# Window_Comparator.net
KiCad netlist of a schematic drawn in Altium Designer
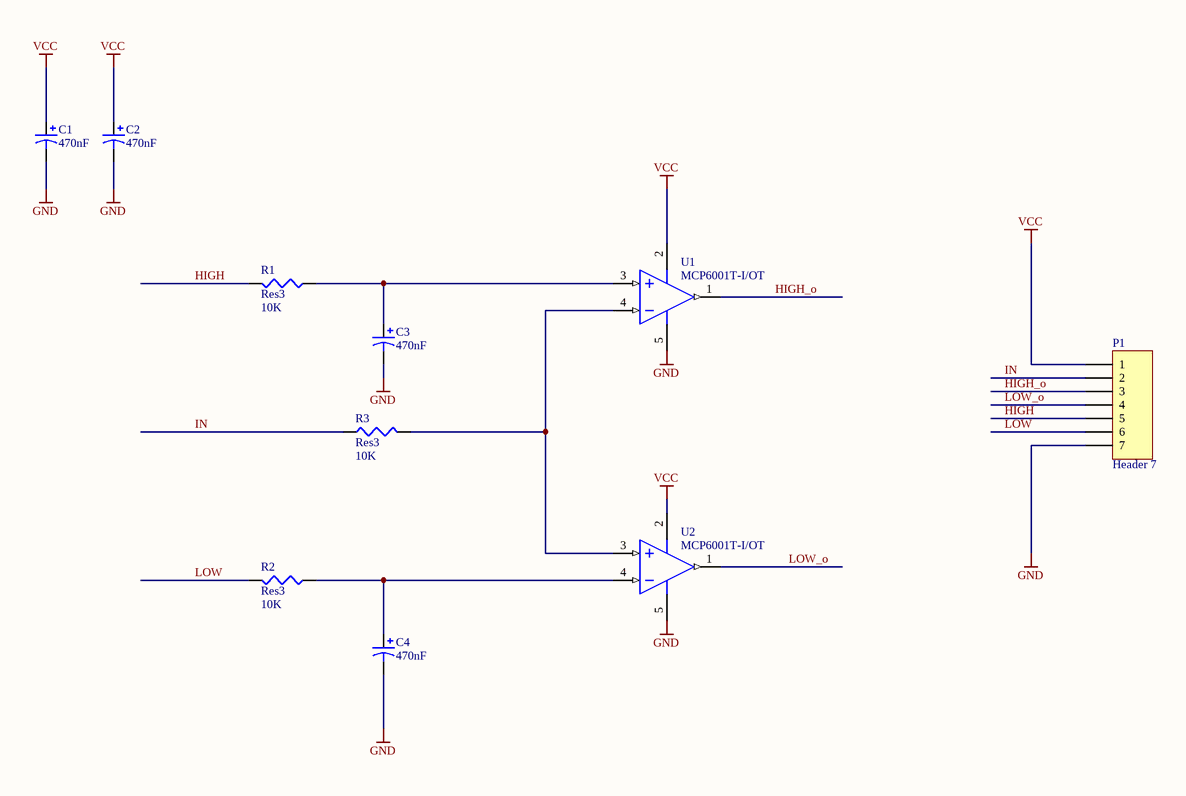
[diagram p0: Window Comparator.SchDoc]

(export (version "E")
  (design (tool "Eeschema 10.0.6"))
  (components
    (comp (ref "C1")
      (value "470nF")
      (footprint "C0805")
      (description "Polarized Capacitor (Surface Mount)")
      (fields (field (name "Comment") "Cap Pol3") (field (name "PUBLISHER") "Altium Limited"))
      (libsource (lib "Miscellaneous Devices") (part "Cap Pol3"))
    )
    (comp (ref "C2")
      (value "470nF")
      (footprint "C0805")
      (description "Polarized Capacitor (Surface Mount)")
      (fields (field (name "Comment") "Cap Pol3") (field (name "PUBLISHER") "Altium Limited"))
      (libsource (lib "Miscellaneous Devices") (part "Cap Pol3"))
    )
    (comp (ref "C3")
      (value "470nF")
      (footprint "C0805")
      (description "Polarized Capacitor (Surface Mount)")
      (fields (field (name "Comment") "Cap Pol3") (field (name "PUBLISHER") "Altium Limited"))
      (libsource (lib "Miscellaneous Devices") (part "Cap Pol3"))
    )
    (comp (ref "C4")
      (value "470nF")
      (footprint "C0805")
      (description "Polarized Capacitor (Surface Mount)")
      (fields (field (name "Comment") "Cap Pol3") (field (name "PUBLISHER") "Altium Limited"))
      (libsource (lib "Miscellaneous Devices") (part "Cap Pol3"))
    )
    (comp (ref "P1")
      (value "Header 7")
      (footprint "HDR1X7")
      (description "Header, 7-Pin")
      (fields (field (name "PUBLISHER") "Altium Limited"))
      (libsource (lib "Miscellaneous Connectors") (part "Header 7"))
    )
    (comp (ref "R1")
      (value "Res3")
      (footprint "J1-0603")
      (description "Resistor")
      (fields (field (name "ALTIUM_VALUE") "10K") (field (name "PUBLISHER") "Altium Limited"))
      (libsource (lib "Miscellaneous Devices") (part "Res3"))
    )
    (comp (ref "R2")
      (value "Res3")
      (footprint "J1-0603")
      (description "Resistor")
      (fields (field (name "ALTIUM_VALUE") "10K") (field (name "PUBLISHER") "Altium Limited"))
      (libsource (lib "Miscellaneous Devices") (part "Res3"))
    )
    (comp (ref "R3")
      (value "Res3")
      (footprint "J1-0603")
      (description "Resistor")
      (fields (field (name "ALTIUM_VALUE") "10K") (field (name "PUBLISHER") "Altium Limited"))
      (libsource (lib "Miscellaneous Devices") (part "Res3"))
    )
    (comp (ref "U1")
      (value "MCP6001T-I/OT")
      (footprint "SOT-23-OT5_N")
      (description "1 MHz, Low-Power Operational Amplifier, 5-Pin SOT-23, Industrial Temperature, Tape and Reel")
      (fields (field (name "PUBLISHER") "Altium Limited"))
      (libsource (lib "Microchip Linear Devices") (part "MCP6001T-I/OT"))
    )
    (comp (ref "U2")
      (value "MCP6001T-I/OT")
      (footprint "SOT-23-OT5_N")
      (description "1 MHz, Low-Power Operational Amplifier, 5-Pin SOT-23, Industrial Temperature, Tape and Reel")
      (fields (field (name "PUBLISHER") "Altium Limited"))
      (libsource (lib "Microchip Linear Devices") (part "MCP6001T-I/OT"))
    )
  )
  (nets
    (net (code "1") (name "/HIGH") (class "Default")
      (node (ref "P1") (pin "5") (pinfunction "5_5") (pintype "passive"))
      (node (ref "R1") (pin "2") (pinfunction "2_2") (pintype "passive"))
    )
    (net (code "2") (name "/HIGH_o") (class "Default")
      (node (ref "P1") (pin "3") (pinfunction "3_3") (pintype "passive"))
      (node (ref "U1") (pin "1") (pinfunction "VOUT_1") (pintype "output"))
    )
    (net (code "3") (name "/IN") (class "Default")
      (node (ref "P1") (pin "2") (pinfunction "2_2") (pintype "passive"))
      (node (ref "R3") (pin "1") (pinfunction "1_1") (pintype "passive"))
    )
    (net (code "4") (name "/LOW") (class "Default")
      (node (ref "P1") (pin "6") (pinfunction "6_6") (pintype "passive"))
      (node (ref "R2") (pin "2") (pinfunction "2_2") (pintype "passive"))
    )
    (net (code "5") (name "/LOW_o") (class "Default")
      (node (ref "P1") (pin "4") (pinfunction "4_4") (pintype "passive"))
      (node (ref "U2") (pin "1") (pinfunction "VOUT_1") (pintype "output"))
    )
    (net (code "6") (name "GND") (class "Default")
      (node (ref "C1") (pin "2") (pinfunction "2_2") (pintype "passive"))
      (node (ref "C2") (pin "2") (pinfunction "2_2") (pintype "passive"))
      (node (ref "C3") (pin "2") (pinfunction "2_2") (pintype "passive"))
      (node (ref "C4") (pin "2") (pinfunction "2_2") (pintype "passive"))
      (node (ref "P1") (pin "7") (pinfunction "7_7") (pintype "passive"))
      (node (ref "U1") (pin "5") (pinfunction "VDD_5") (pintype "power_in"))
      (node (ref "U2") (pin "5") (pinfunction "VDD_5") (pintype "power_in"))
    )
    (net (code "7") (name "Net-(U1-VIN+)") (class "Default")
      (node (ref "C3") (pin "1") (pinfunction "1_1") (pintype "passive"))
      (node (ref "R1") (pin "1") (pinfunction "1_1") (pintype "passive"))
      (node (ref "U1") (pin "3") (pinfunction "VIN+_3") (pintype "input"))
    )
    (net (code "8") (name "Net-(U1-VIN-)") (class "Default")
      (node (ref "R3") (pin "2") (pinfunction "2_2") (pintype "passive"))
      (node (ref "U1") (pin "4") (pinfunction "VIN-_4") (pintype "input"))
      (node (ref "U2") (pin "3") (pinfunction "VIN+_3") (pintype "input"))
    )
    (net (code "9") (name "Net-(U2-VIN-)") (class "Default")
      (node (ref "C4") (pin "1") (pinfunction "1_1") (pintype "passive"))
      (node (ref "R2") (pin "1") (pinfunction "1_1") (pintype "passive"))
      (node (ref "U2") (pin "4") (pinfunction "VIN-_4") (pintype "input"))
    )
    (net (code "10") (name "VCC") (class "Default")
      (node (ref "C1") (pin "1") (pinfunction "1_1") (pintype "passive"))
      (node (ref "C2") (pin "1") (pinfunction "1_1") (pintype "passive"))
      (node (ref "P1") (pin "1") (pinfunction "1_1") (pintype "passive"))
      (node (ref "U1") (pin "2") (pinfunction "VSS_2") (pintype "power_in"))
      (node (ref "U2") (pin "2") (pinfunction "VSS_2") (pintype "power_in"))
    )
  )
)
